# MOTORSHIELDV3_HETPRO_v2.net
KiCad netlist of a schematic drawn in EAGLE
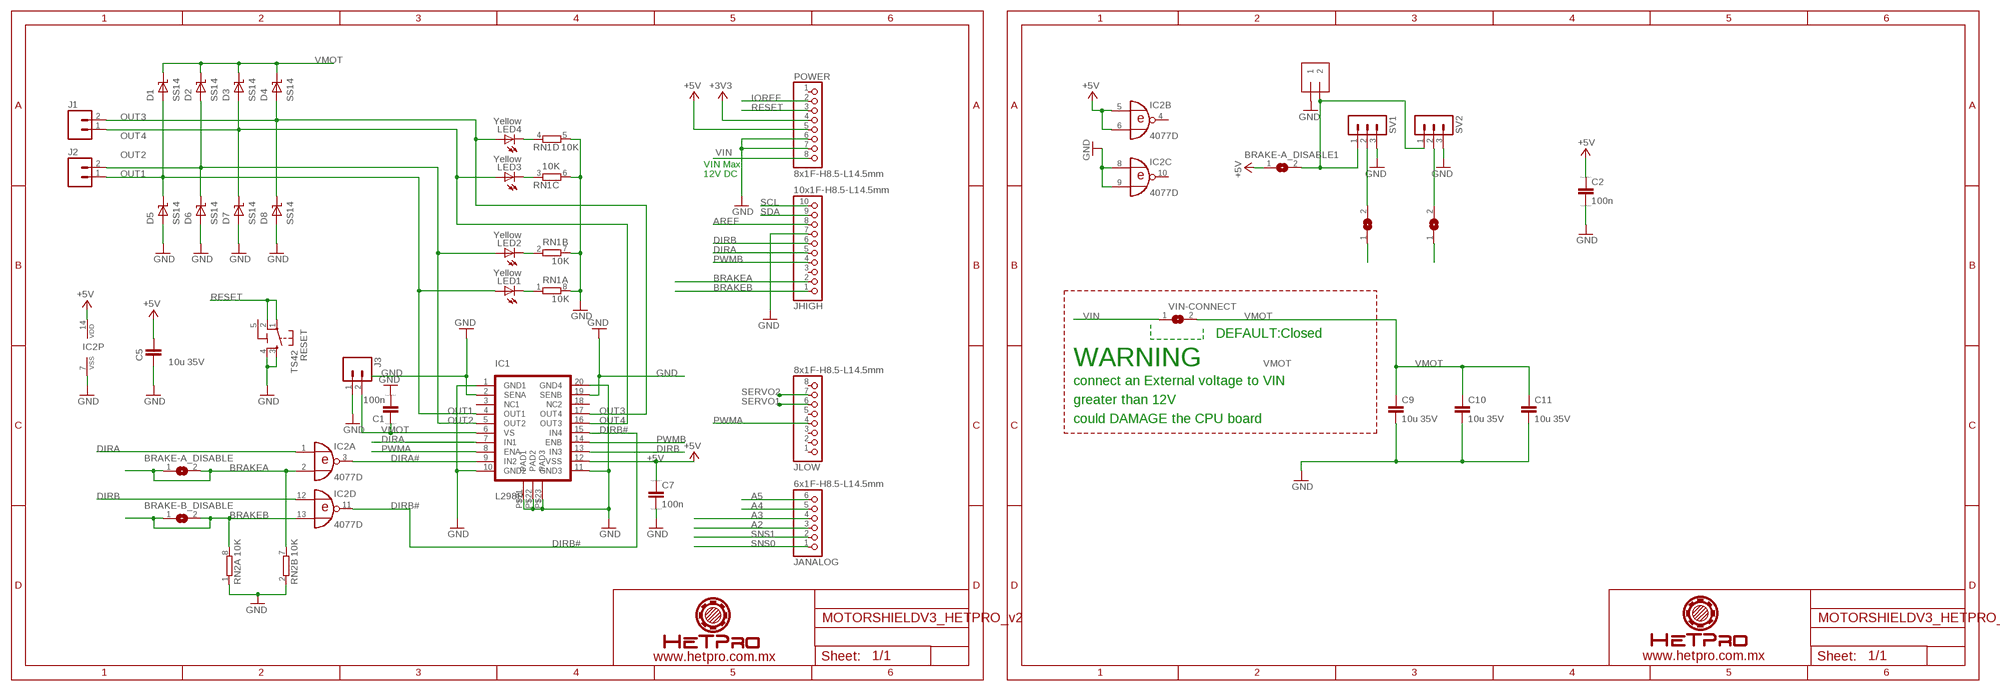
[diagram p0: schematic, sheet 1]

(export (version "E")
  (design (tool "Eeschema 10.0.6"))
  (components
    (comp (ref "BRAKE-A_DISABLE")
      (value "SJ")
      (footprint "eagle-import:SJ")
      (libsource (lib "eagle-import") (part "SJ"))
    )
    (comp (ref "BRAKE-A_DISABLE1")
      (value "SJ")
      (footprint "eagle-import:SJ")
      (libsource (lib "eagle-import") (part "SJ"))
    )
    (comp (ref "BRAKE-A_DISABLE2")
      (value "SJ")
      (footprint "eagle-import:SJ")
      (libsource (lib "eagle-import") (part "SJ"))
    )
    (comp (ref "BRAKE-A_DISABLE3")
      (value "SJ")
      (footprint "eagle-import:SJ")
      (libsource (lib "eagle-import") (part "SJ"))
    )
    (comp (ref "BRAKE-B_DISABLE")
      (value "SJ")
      (footprint "eagle-import:SJ")
      (libsource (lib "eagle-import") (part "SJ"))
    )
    (comp (ref "C1")
      (value "100n")
      (footprint "eagle-import:C0603")
      (libsource (lib "eagle-import") (part "CC0603"))
    )
    (comp (ref "C2")
      (value "100n")
      (footprint "eagle-import:C0603")
      (libsource (lib "eagle-import") (part "CC0603"))
    )
    (comp (ref "C5")
      (value "10u 35V")
      (footprint "eagle-import:C1210")
      (libsource (lib "eagle-import") (part "C-EUC1210"))
    )
    (comp (ref "C7")
      (value "100n")
      (footprint "eagle-import:C0603")
      (libsource (lib "eagle-import") (part "CC0603"))
    )
    (comp (ref "C9")
      (value "10u 35V")
      (footprint "eagle-import:C1210")
      (libsource (lib "eagle-import") (part "C-EUC1210"))
    )
    (comp (ref "C10")
      (value "10u 35V")
      (footprint "eagle-import:C1210")
      (libsource (lib "eagle-import") (part "C-EUC1210"))
    )
    (comp (ref "C11")
      (value "10u 35V")
      (footprint "eagle-import:C1210")
      (libsource (lib "eagle-import") (part "C-EUC1210"))
    )
    (comp (ref "D1")
      (value "SS14")
      (footprint "eagle-import:SMA")
      (libsource (lib "eagle-import") (part "SS14"))
    )
    (comp (ref "D2")
      (value "SS14")
      (footprint "eagle-import:SMA")
      (libsource (lib "eagle-import") (part "SS14"))
    )
    (comp (ref "D3")
      (value "SS14")
      (footprint "eagle-import:SMA")
      (libsource (lib "eagle-import") (part "SS14"))
    )
    (comp (ref "D4")
      (value "SS14")
      (footprint "eagle-import:SMA")
      (libsource (lib "eagle-import") (part "SS14"))
    )
    (comp (ref "D5")
      (value "SS14")
      (footprint "eagle-import:SMA")
      (libsource (lib "eagle-import") (part "SS14"))
    )
    (comp (ref "D6")
      (value "SS14")
      (footprint "eagle-import:SMA")
      (libsource (lib "eagle-import") (part "SS14"))
    )
    (comp (ref "D7")
      (value "SS14")
      (footprint "eagle-import:SMA")
      (libsource (lib "eagle-import") (part "SS14"))
    )
    (comp (ref "D8")
      (value "SS14")
      (footprint "eagle-import:SMA")
      (libsource (lib "eagle-import") (part "SS14"))
    )
    (comp (ref "IC1")
      (value "L298P")
      (footprint "eagle-import:POWER-SO20")
      (libsource (lib "eagle-import") (part "L298P"))
    )
    (comp (ref "IC2")
      (value "4077D")
      (footprint "eagle-import:SO14")
      (libsource (lib "eagle-import") (part "4077D"))
    )
    (comp (ref "J1")
      (value "M025MM")
      (footprint "eagle-import:SCREWTERMINAL-5MM-2")
      (libsource (lib "eagle-import") (part "M025MM"))
    )
    (comp (ref "J2")
      (value "M025MM")
      (footprint "eagle-import:SCREWTERMINAL-5MM-2")
      (libsource (lib "eagle-import") (part "M025MM"))
    )
    (comp (ref "J3")
      (value "M025MM")
      (footprint "eagle-import:SCREWTERMINAL-5MM-2")
      (libsource (lib "eagle-import") (part "M025MM"))
    )
    (comp (ref "J4")
      (value "1X2-3.5MM")
      (footprint "eagle-import:1X2-3.5MM")
      (libsource (lib "eagle-import") (part "1X2-3.5MM"))
    )
    (comp (ref "JANALOG")
      (value "6x1F-H8.5-L14.5mm")
      (footprint "eagle-import:1X06-TH")
      (libsource (lib "eagle-import") (part "PINHD-1X6TH"))
    )
    (comp (ref "JHIGH")
      (value "10x1F-H8.5-L14.5mm")
      (footprint "eagle-import:1X10-TH")
      (libsource (lib "eagle-import") (part "PINHD-1X10TH"))
    )
    (comp (ref "JLOW")
      (value "8x1F-H8.5-L14.5mm")
      (footprint "eagle-import:1X08-TH")
      (libsource (lib "eagle-import") (part "PINHD-1X8TH"))
    )
    (comp (ref "LED1")
      (value "Yellow")
      (footprint "eagle-import:LED-1206")
      (libsource (lib "eagle-import") (part "LED1206"))
    )
    (comp (ref "LED2")
      (value "Yellow")
      (footprint "eagle-import:LED-1206")
      (libsource (lib "eagle-import") (part "LED1206"))
    )
    (comp (ref "LED3")
      (value "Yellow")
      (footprint "eagle-import:LED-1206")
      (libsource (lib "eagle-import") (part "LED1206"))
    )
    (comp (ref "LED4")
      (value "Yellow")
      (footprint "eagle-import:LED-1206")
      (libsource (lib "eagle-import") (part "LED1206"))
    )
    (comp (ref "POWER")
      (value "8x1F-H8.5-L14.5mm")
      (footprint "eagle-import:1X08-TH")
      (libsource (lib "eagle-import") (part "PINHD-1X8TH"))
    )
    (comp (ref "RESET")
      (value "TS42")
      (footprint "eagle-import:TS42")
      (libsource (lib "eagle-import") (part "TS42"))
    )
    (comp (ref "RN1")
      (value "10K")
      (footprint "eagle-import:CAY16")
      (libsource (lib "eagle-import") (part "4R-NCAY16"))
    )
    (comp (ref "RN2")
      (value "10K")
      (footprint "eagle-import:CAY16")
      (libsource (lib "eagle-import") (part "4R-NCAY16"))
    )
    (comp (ref "SV1")
      (value "MA03-1")
      (footprint "eagle-import:MA03-1")
      (libsource (lib "eagle-import") (part "MA03-1"))
    )
    (comp (ref "SV2")
      (value "MA03-1")
      (footprint "eagle-import:MA03-1")
      (libsource (lib "eagle-import") (part "MA03-1"))
    )
    (comp (ref "VIN-CONNECT")
      (value "SJ")
      (footprint "eagle-import:SJ")
      (libsource (lib "eagle-import") (part "SJ"))
    )
  )
  (nets
    (net (code "1") (name "+3V3") (class "Default")
      (node (ref "POWER") (pin "4") (pinfunction "4_4") (pintype "passive"))
    )
    (net (code "2") (name "+5V") (class "Default")
      (node (ref "BRAKE-A_DISABLE1") (pin "1") (pinfunction "1_1") (pintype "passive"))
      (node (ref "C2") (pin "1") (pinfunction "1_1") (pintype "passive"))
      (node (ref "C5") (pin "1") (pinfunction "1_1") (pintype "passive"))
      (node (ref "C7") (pin "1") (pinfunction "1_1") (pintype "passive"))
      (node (ref "IC1") (pin "P$12") (pinfunction "VSS_P$12") (pintype "power_in"))
      (node (ref "IC2") (pin "14") (pinfunction "VDD_14") (pintype "power_in"))
      (node (ref "IC2") (pin "5") (pinfunction "I0_5") (pintype "input"))
      (node (ref "IC2") (pin "6") (pinfunction "I1_6") (pintype "input"))
      (node (ref "POWER") (pin "5") (pinfunction "5_5") (pintype "passive"))
    )
    (net (code "3") (name "/5-GND") (class "Default")
      (node (ref "RESET") (pin "5") (pinfunction "5-GND_5") (pintype "power_in"))
    )
    (net (code "4") (name "/A2") (class "Default")
      (node (ref "JANALOG") (pin "3") (pinfunction "3_3") (pintype "passive"))
    )
    (net (code "5") (name "/A3") (class "Default")
      (node (ref "JANALOG") (pin "4") (pinfunction "4_4") (pintype "passive"))
    )
    (net (code "6") (name "/A4") (class "Default")
      (node (ref "JANALOG") (pin "5") (pinfunction "5_5") (pintype "passive"))
    )
    (net (code "7") (name "/A5") (class "Default")
      (node (ref "JANALOG") (pin "6") (pinfunction "6_6") (pintype "passive"))
    )
    (net (code "8") (name "/AREF") (class "Default")
      (node (ref "JHIGH") (pin "8") (pinfunction "8_8") (pintype "passive"))
    )
    (net (code "9") (name "/BRAKEA") (class "Default")
      (node (ref "BRAKE-A_DISABLE") (pin "1") (pinfunction "1_1") (pintype "passive"))
      (node (ref "BRAKE-A_DISABLE") (pin "2") (pinfunction "2_2") (pintype "passive"))
      (node (ref "IC2") (pin "2") (pinfunction "I1_2") (pintype "input"))
      (node (ref "JHIGH") (pin "2") (pinfunction "2_2") (pintype "passive"))
      (node (ref "RN2") (pin "7") (pinfunction "2_7") (pintype "passive"))
    )
    (net (code "10") (name "/BRAKEB") (class "Default")
      (node (ref "BRAKE-B_DISABLE") (pin "1") (pinfunction "1_1") (pintype "passive"))
      (node (ref "BRAKE-B_DISABLE") (pin "2") (pinfunction "2_2") (pintype "passive"))
      (node (ref "IC2") (pin "13") (pinfunction "I1_13") (pintype "input"))
      (node (ref "JHIGH") (pin "1") (pinfunction "1_1") (pintype "passive"))
      (node (ref "RN2") (pin "8") (pinfunction "2_8") (pintype "passive"))
    )
    (net (code "11") (name "/DIRA") (class "Default")
      (node (ref "IC1") (pin "P$7") (pinfunction "IN1_P$7") (pintype "input"))
      (node (ref "IC2") (pin "1") (pinfunction "I0_1") (pintype "input"))
      (node (ref "JHIGH") (pin "5") (pinfunction "5_5") (pintype "passive"))
    )
    (net (code "12") (name "/DIRA#") (class "Default")
      (node (ref "IC1") (pin "P$9") (pinfunction "IN2_P$9") (pintype "input"))
      (node (ref "IC2") (pin "3") (pinfunction "O_3") (pintype "output"))
    )
    (net (code "13") (name "/DIRB") (class "Default")
      (node (ref "IC1") (pin "P$13") (pinfunction "IN3_P$13") (pintype "input"))
      (node (ref "IC2") (pin "12") (pinfunction "I0_12") (pintype "input"))
      (node (ref "JHIGH") (pin "6") (pinfunction "6_6") (pintype "passive"))
    )
    (net (code "14") (name "/DIRB#") (class "Default")
      (node (ref "IC1") (pin "P$15") (pinfunction "IN4_P$15") (pintype "input"))
      (node (ref "IC2") (pin "11") (pinfunction "O_11") (pintype "output"))
    )
    (net (code "15") (name "/IOREF") (class "Default")
      (node (ref "POWER") (pin "2") (pinfunction "2_2") (pintype "passive"))
    )
    (net (code "16") (name "/OUT1") (class "Default")
      (node (ref "D1") (pin "P$2") (pinfunction "A_P$2") (pintype "bidirectional"))
      (node (ref "D5") (pin "P$1") (pinfunction "K_P$1") (pintype "bidirectional"))
      (node (ref "IC1") (pin "P$4") (pinfunction "OUT1_P$4") (pintype "output"))
      (node (ref "J2") (pin "1") (pinfunction "1_1") (pintype "passive"))
      (node (ref "LED1") (pin "A") (pinfunction "A_A") (pintype "passive"))
    )
    (net (code "17") (name "/OUT2") (class "Default")
      (node (ref "D2") (pin "P$2") (pinfunction "A_P$2") (pintype "bidirectional"))
      (node (ref "D6") (pin "P$1") (pinfunction "K_P$1") (pintype "bidirectional"))
      (node (ref "IC1") (pin "P$5") (pinfunction "OUT2_P$5") (pintype "output"))
      (node (ref "J2") (pin "2") (pinfunction "2_2") (pintype "passive"))
      (node (ref "LED2") (pin "A") (pinfunction "A_A") (pintype "passive"))
    )
    (net (code "18") (name "/OUT3") (class "Default")
      (node (ref "D4") (pin "P$2") (pinfunction "A_P$2") (pintype "bidirectional"))
      (node (ref "D8") (pin "P$1") (pinfunction "K_P$1") (pintype "bidirectional"))
      (node (ref "IC1") (pin "P$17") (pinfunction "OUT4_P$17") (pintype "output"))
      (node (ref "J1") (pin "2") (pinfunction "2_2") (pintype "passive"))
      (node (ref "LED4") (pin "A") (pinfunction "A_A") (pintype "passive"))
    )
    (net (code "19") (name "/OUT4") (class "Default")
      (node (ref "D3") (pin "P$2") (pinfunction "A_P$2") (pintype "bidirectional"))
      (node (ref "D7") (pin "P$1") (pinfunction "K_P$1") (pintype "bidirectional"))
      (node (ref "IC1") (pin "P$16") (pinfunction "OUT3_P$16") (pintype "output"))
      (node (ref "J1") (pin "1") (pinfunction "1_1") (pintype "passive"))
      (node (ref "LED3") (pin "A") (pinfunction "A_A") (pintype "passive"))
    )
    (net (code "20") (name "/PWMA") (class "Default")
      (node (ref "IC1") (pin "P$8") (pinfunction "ENA_P$8") (pintype "input"))
      (node (ref "JLOW") (pin "4") (pinfunction "4_4") (pintype "passive"))
    )
    (net (code "21") (name "/PWMB") (class "Default")
      (node (ref "IC1") (pin "P$14") (pinfunction "ENB_P$14") (pintype "input"))
      (node (ref "JHIGH") (pin "4") (pinfunction "4_4") (pintype "passive"))
    )
    (net (code "22") (name "/RESET") (class "Default")
      (node (ref "POWER") (pin "3") (pinfunction "3_3") (pintype "passive"))
      (node (ref "RESET") (pin "1") (pinfunction "1_1") (pintype "passive"))
      (node (ref "RESET") (pin "2") (pinfunction "2_2") (pintype "passive"))
    )
    (net (code "23") (name "/SCL") (class "Default")
      (node (ref "JHIGH") (pin "10") (pinfunction "10_10") (pintype "passive"))
    )
    (net (code "24") (name "/SDA") (class "Default")
      (node (ref "JHIGH") (pin "9") (pinfunction "9_9") (pintype "passive"))
    )
    (net (code "25") (name "/SERVO1") (class "Default")
      (node (ref "BRAKE-A_DISABLE2") (pin "1") (pinfunction "1_1") (pintype "passive"))
      (node (ref "JLOW") (pin "6") (pinfunction "6_6") (pintype "passive"))
    )
    (net (code "26") (name "/SERVO2") (class "Default")
      (node (ref "BRAKE-A_DISABLE3") (pin "1") (pinfunction "1_1") (pintype "passive"))
      (node (ref "JLOW") (pin "7") (pinfunction "7_7") (pintype "passive"))
    )
    (net (code "27") (name "/SNS0") (class "Default")
      (node (ref "JANALOG") (pin "1") (pinfunction "1_1") (pintype "passive"))
    )
    (net (code "28") (name "/SNS1") (class "Default")
      (node (ref "JANALOG") (pin "2") (pinfunction "2_2") (pintype "passive"))
    )
    (net (code "29") (name "/VIN") (class "Default")
      (node (ref "POWER") (pin "8") (pinfunction "8_8") (pintype "passive"))
      (node (ref "VIN-CONNECT") (pin "1") (pinfunction "1_1") (pintype "passive"))
    )
    (net (code "30") (name "/VMOT") (class "Default")
      (node (ref "C1") (pin "1") (pinfunction "1_1") (pintype "passive"))
      (node (ref "C10") (pin "1") (pinfunction "1_1") (pintype "passive"))
      (node (ref "C11") (pin "1") (pinfunction "1_1") (pintype "passive"))
      (node (ref "C9") (pin "1") (pinfunction "1_1") (pintype "passive"))
      (node (ref "D1") (pin "P$1") (pinfunction "K_P$1") (pintype "bidirectional"))
      (node (ref "D2") (pin "P$1") (pinfunction "K_P$1") (pintype "bidirectional"))
      (node (ref "D3") (pin "P$1") (pinfunction "K_P$1") (pintype "bidirectional"))
      (node (ref "D4") (pin "P$1") (pinfunction "K_P$1") (pintype "bidirectional"))
      (node (ref "IC1") (pin "P$6") (pinfunction "VS_P$6") (pintype "power_in"))
      (node (ref "J3") (pin "2") (pinfunction "2_2") (pintype "passive"))
      (node (ref "VIN-CONNECT") (pin "2") (pinfunction "2_2") (pintype "passive"))
    )
    (net (code "31") (name "GND") (class "Default")
      (node (ref "C1") (pin "2") (pinfunction "2_2") (pintype "passive"))
      (node (ref "C10") (pin "2") (pinfunction "2_2") (pintype "passive"))
      (node (ref "C11") (pin "2") (pinfunction "2_2") (pintype "passive"))
      (node (ref "C2") (pin "2") (pinfunction "2_2") (pintype "passive"))
      (node (ref "C5") (pin "2") (pinfunction "2_2") (pintype "passive"))
      (node (ref "C7") (pin "2") (pinfunction "2_2") (pintype "passive"))
      (node (ref "C9") (pin "2") (pinfunction "2_2") (pintype "passive"))
      (node (ref "D5") (pin "P$2") (pinfunction "A_P$2") (pintype "bidirectional"))
      (node (ref "D6") (pin "P$2") (pinfunction "A_P$2") (pintype "bidirectional"))
      (node (ref "D7") (pin "P$2") (pinfunction "A_P$2") (pintype "bidirectional"))
      (node (ref "D8") (pin "P$2") (pinfunction "A_P$2") (pintype "bidirectional"))
      (node (ref "IC1") (pin "P$1") (pinfunction "GND1_P$1") (pintype "power_in"))
      (node (ref "IC1") (pin "P$10") (pinfunction "GND2_P$10") (pintype "power_in"))
      (node (ref "IC1") (pin "P$11") (pinfunction "GND3_P$11") (pintype "power_in"))
      (node (ref "IC1") (pin "P$19") (pinfunction "SENB_P$19") (pintype "input"))
      (node (ref "IC1") (pin "P$2") (pinfunction "SENA_P$2") (pintype "input"))
      (node (ref "IC1") (pin "P$20") (pinfunction "GND4_P$20") (pintype "power_in"))
      (node (ref "IC1") (pin "P$21") (pinfunction "PAD1_P$21") (pintype "passive"))
      (node (ref "IC1") (pin "P$22") (pinfunction "PAD2_P$22") (pintype "passive"))
      (node (ref "IC1") (pin "P$23") (pinfunction "PAD3_P$23") (pintype "passive"))
      (node (ref "IC2") (pin "7") (pinfunction "VSS_7") (pintype "power_in"))
      (node (ref "IC2") (pin "8") (pinfunction "I0_8") (pintype "input"))
      (node (ref "IC2") (pin "9") (pinfunction "I1_9") (pintype "input"))
      (node (ref "J3") (pin "1") (pinfunction "1_1") (pintype "passive"))
      (node (ref "J4") (pin "1") (pinfunction "1_1") (pintype "passive"))
      (node (ref "JHIGH") (pin "7") (pinfunction "7_7") (pintype "passive"))
      (node (ref "POWER") (pin "6") (pinfunction "6_6") (pintype "passive"))
      (node (ref "POWER") (pin "7") (pinfunction "7_7") (pintype "passive"))
      (node (ref "RESET") (pin "3") (pinfunction "3_3") (pintype "passive"))
      (node (ref "RESET") (pin "4") (pinfunction "4_4") (pintype "passive"))
      (node (ref "RN1") (pin "5") (pinfunction "2_5") (pintype "passive"))
      (node (ref "RN1") (pin "6") (pinfunction "2_6") (pintype "passive"))
      (node (ref "RN1") (pin "7") (pinfunction "2_7") (pintype "passive"))
      (node (ref "RN1") (pin "8") (pinfunction "2_8") (pintype "passive"))
      (node (ref "RN2") (pin "1") (pinfunction "1_1") (pintype "passive"))
      (node (ref "RN2") (pin "2") (pinfunction "1_2") (pintype "passive"))
      (node (ref "SV1") (pin "3") (pinfunction "3_3") (pintype "passive"))
      (node (ref "SV2") (pin "3") (pinfunction "3_3") (pintype "passive"))
    )
    (net (code "32") (name "Net-(BRAKE-A_DISABLE1-Pad2)") (class "Default")
      (node (ref "BRAKE-A_DISABLE1") (pin "2") (pinfunction "2_2") (pintype "passive"))
      (node (ref "J4") (pin "2") (pinfunction "2_2") (pintype "passive"))
      (node (ref "SV1") (pin "1") (pinfunction "1_1") (pintype "passive"))
      (node (ref "SV2") (pin "1") (pinfunction "1_1") (pintype "passive"))
    )
    (net (code "33") (name "Net-(BRAKE-A_DISABLE2-Pad2)") (class "Default")
      (node (ref "BRAKE-A_DISABLE2") (pin "2") (pinfunction "2_2") (pintype "passive"))
      (node (ref "SV1") (pin "2") (pinfunction "2_2") (pintype "passive"))
    )
    (net (code "34") (name "Net-(BRAKE-A_DISABLE3-Pad2)") (class "Default")
      (node (ref "BRAKE-A_DISABLE3") (pin "2") (pinfunction "2_2") (pintype "passive"))
      (node (ref "SV2") (pin "2") (pinfunction "2_2") (pintype "passive"))
    )
    (net (code "35") (name "Net-(LED1-PadC)") (class "Default")
      (node (ref "LED1") (pin "C") (pinfunction "C_C") (pintype "passive"))
      (node (ref "RN1") (pin "1") (pinfunction "1_1") (pintype "passive"))
    )
    (net (code "36") (name "Net-(RN1B-1)") (class "Default")
      (node (ref "LED2") (pin "C") (pinfunction "C_C") (pintype "passive"))
      (node (ref "RN1") (pin "2") (pinfunction "1_2") (pintype "passive"))
    )
    (net (code "37") (name "Net-(RN1C-1)") (class "Default")
      (node (ref "LED3") (pin "C") (pinfunction "C_C") (pintype "passive"))
      (node (ref "RN1") (pin "3") (pinfunction "1_3") (pintype "passive"))
    )
    (net (code "38") (name "Net-(RN1D-1)") (class "Default")
      (node (ref "LED4") (pin "C") (pinfunction "C_C") (pintype "passive"))
      (node (ref "RN1") (pin "4") (pinfunction "1_4") (pintype "passive"))
    )
    (net (code "39") (name "unconnected-(IC1-NC1-PadP$3)") (class "Default")
      (node (ref "IC1") (pin "P$3") (pinfunction "NC1_P$3") (pintype "no_connect"))
    )
    (net (code "40") (name "unconnected-(IC1-NC2-PadP$18)") (class "Default")
      (node (ref "IC1") (pin "P$18") (pinfunction "NC2_P$18") (pintype "no_connect"))
    )
    (net (code "41") (name "unconnected-(IC2B-O-Pad4)") (class "Default")
      (node (ref "IC2") (pin "4") (pinfunction "O_4") (pintype "output"))
    )
    (net (code "42") (name "unconnected-(IC2C-O-Pad10)") (class "Default")
      (node (ref "IC2") (pin "10") (pinfunction "O_10") (pintype "output"))
    )
    (net (code "43") (name "unconnected-(JHIGH-Pad3)") (class "Default")
      (node (ref "JHIGH") (pin "3") (pinfunction "3_3") (pintype "passive"))
    )
    (net (code "44") (name "unconnected-(JLOW-Pad1)") (class "Default")
      (node (ref "JLOW") (pin "1") (pinfunction "1_1") (pintype "passive"))
    )
    (net (code "45") (name "unconnected-(JLOW-Pad2)") (class "Default")
      (node (ref "JLOW") (pin "2") (pinfunction "2_2") (pintype "passive"))
    )
    (net (code "46") (name "unconnected-(JLOW-Pad3)") (class "Default")
      (node (ref "JLOW") (pin "3") (pinfunction "3_3") (pintype "passive"))
    )
    (net (code "47") (name "unconnected-(JLOW-Pad5)") (class "Default")
      (node (ref "JLOW") (pin "5") (pinfunction "5_5") (pintype "passive"))
    )
    (net (code "48") (name "unconnected-(JLOW-Pad8)") (class "Default")
      (node (ref "JLOW") (pin "8") (pinfunction "8_8") (pintype "passive"))
    )
    (net (code "49") (name "unconnected-(POWER-Pad1)") (class "Default")
      (node (ref "POWER") (pin "1") (pinfunction "1_1") (pintype "passive"))
    )
  )
)
